# main.net
KiCad netlist of a schematic drawn in EAGLE
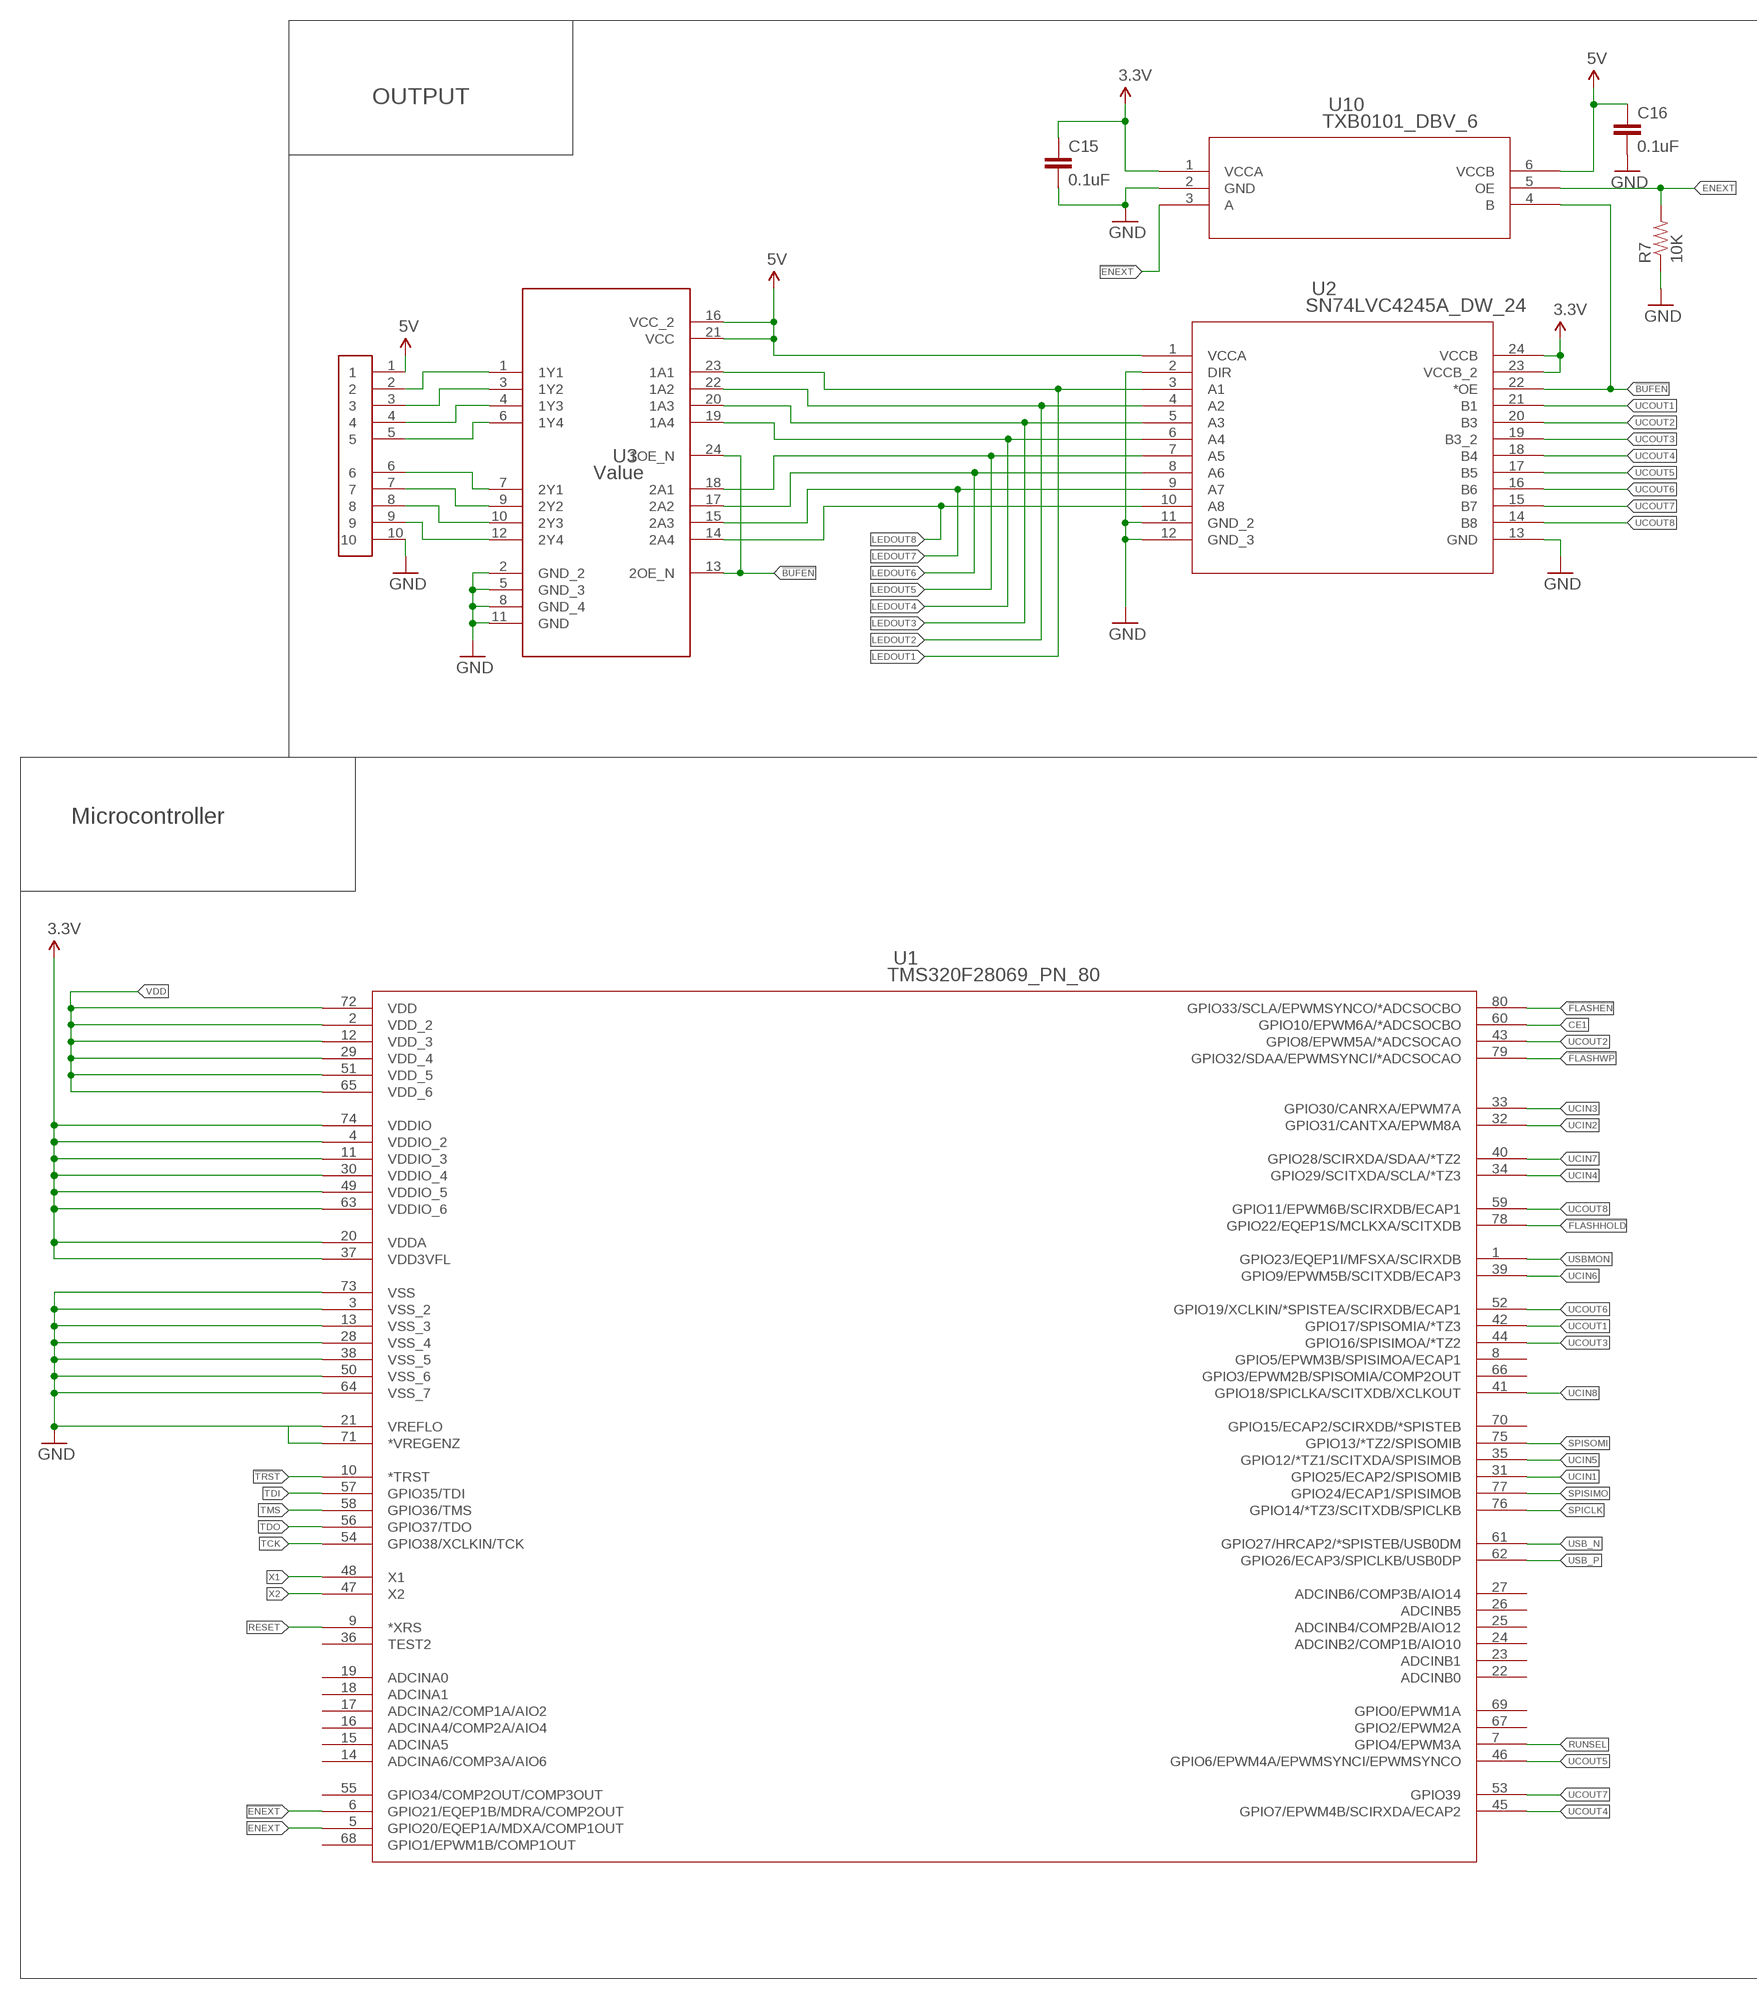
[diagram p0: schematic, sheet 1, part 1 of 2]
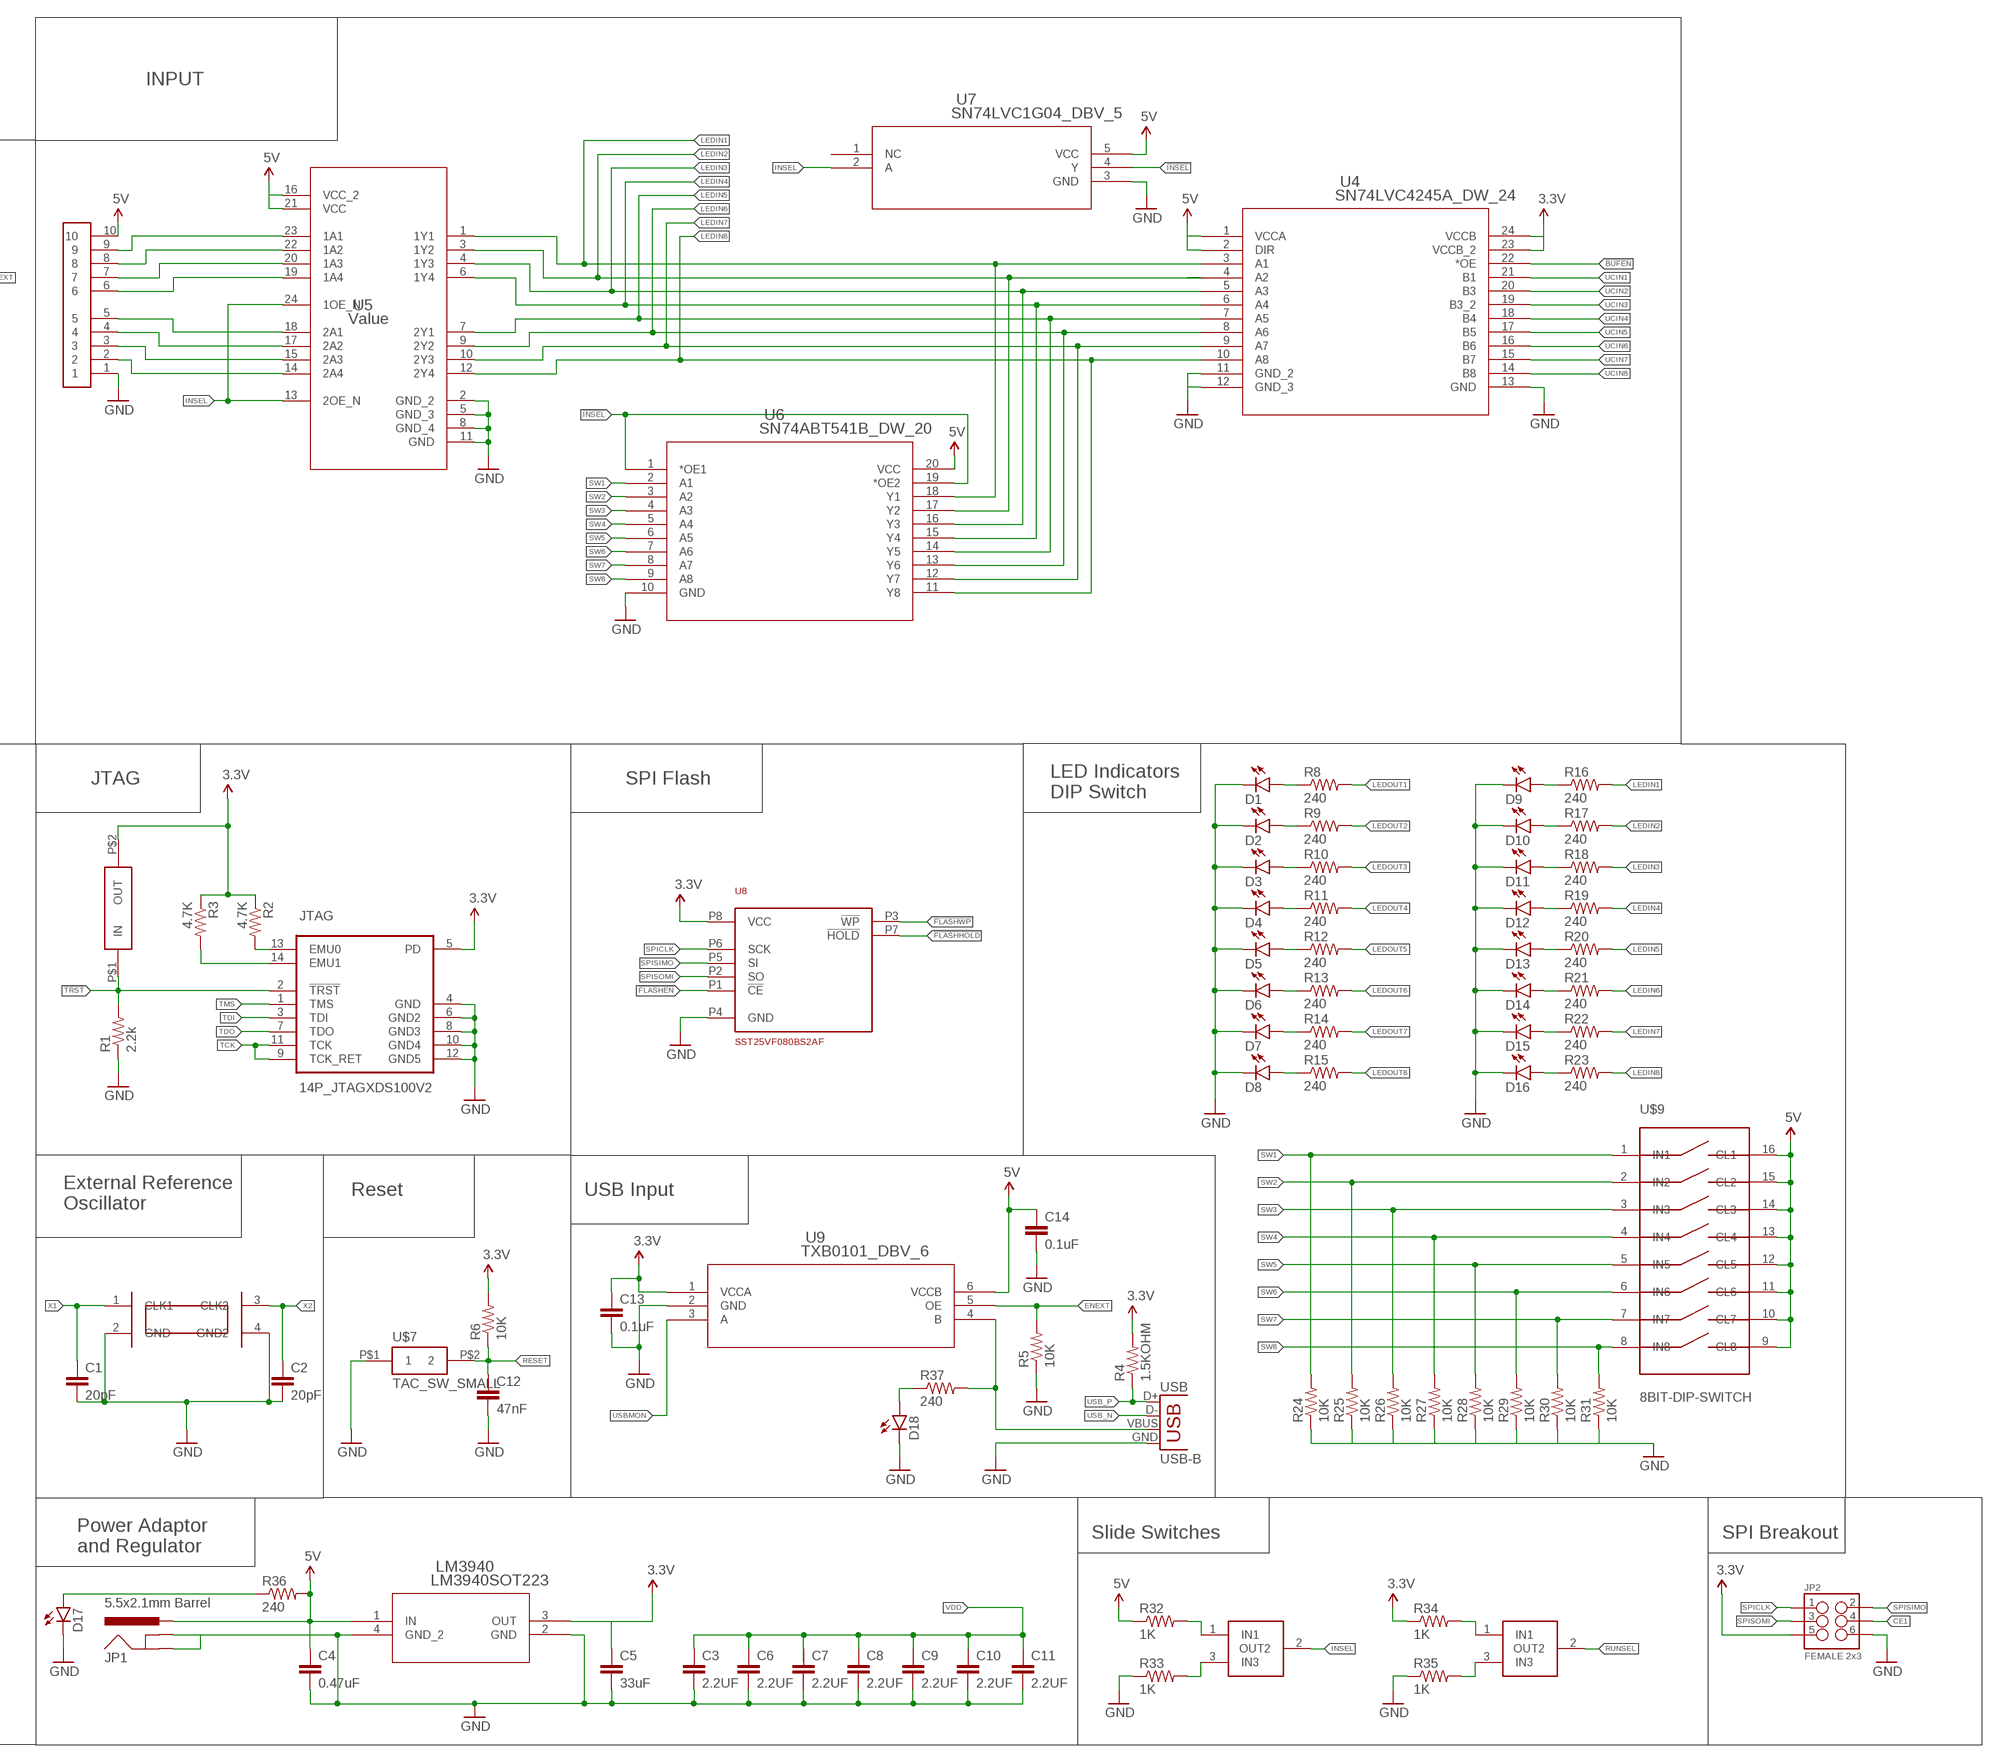
[diagram p1: schematic, sheet 1, part 2 of 2]

(export (version "E")
  (design (tool "Eeschema 10.0.6"))
  (components
    (comp (ref "!TRST!")
      (value "DIP_SWITCH_1B")
      (footprint "eagle-import:CHS-01B")
      (libsource (lib "eagle-import") (part "DIP_SWITCH_1B"))
    )
    (comp (ref "C1")
      (value "20pF")
      (footprint "eagle-import:0603-CAP")
      (libsource (lib "eagle-import") (part "18PF-50V-5%(0603)"))
    )
    (comp (ref "C2")
      (value "20pF")
      (footprint "eagle-import:0603-CAP")
      (libsource (lib "eagle-import") (part "18PF-50V-5%(0603)"))
    )
    (comp (ref "C3")
      (value "2.2UF")
      (footprint "eagle-import:1206")
      (libsource (lib "eagle-import") (part "2.2UF50V10%(1206)"))
    )
    (comp (ref "C4")
      (value "0.47uF")
      (footprint "eagle-import:0603-CAP")
      (libsource (lib "eagle-import") (part "0.22UF50V-20%,+80%(0603)"))
    )
    (comp (ref "C5")
      (value "33uF")
      (footprint "eagle-import:1206")
      (libsource (lib "eagle-import") (part "1.0UF50V10%(1206)"))
    )
    (comp (ref "C6")
      (value "2.2UF")
      (footprint "eagle-import:1206")
      (libsource (lib "eagle-import") (part "2.2UF50V10%(1206)"))
    )
    (comp (ref "C7")
      (value "2.2UF")
      (footprint "eagle-import:1206")
      (libsource (lib "eagle-import") (part "2.2UF50V10%(1206)"))
    )
    (comp (ref "C8")
      (value "2.2UF")
      (footprint "eagle-import:1206")
      (libsource (lib "eagle-import") (part "2.2UF50V10%(1206)"))
    )
    (comp (ref "C9")
      (value "2.2UF")
      (footprint "eagle-import:1206")
      (libsource (lib "eagle-import") (part "2.2UF50V10%(1206)"))
    )
    (comp (ref "C10")
      (value "2.2UF")
      (footprint "eagle-import:1206")
      (libsource (lib "eagle-import") (part "2.2UF50V10%(1206)"))
    )
    (comp (ref "C11")
      (value "2.2UF")
      (footprint "eagle-import:1206")
      (libsource (lib "eagle-import") (part "2.2UF50V10%(1206)"))
    )
    (comp (ref "C12")
      (value "47nF")
      (footprint "eagle-import:0603-CAP")
      (libsource (lib "eagle-import") (part "47NF(0.047UF/47000PF)-25V-5%(0603)SMD"))
    )
    (comp (ref "C13")
      (value "0.1uF")
      (footprint "eagle-import:1206")
      (libsource (lib "eagle-import") (part "1.0UF50V10%(1206)"))
    )
    (comp (ref "C14")
      (value "0.1uF")
      (footprint "eagle-import:1206")
      (libsource (lib "eagle-import") (part "1.0UF50V10%(1206)"))
    )
    (comp (ref "C15")
      (value "0.1uF")
      (footprint "eagle-import:1206")
      (libsource (lib "eagle-import") (part "1.0UF50V10%(1206)"))
    )
    (comp (ref "C16")
      (value "0.1uF")
      (footprint "eagle-import:1206")
      (libsource (lib "eagle-import") (part "1.0UF50V10%(1206)"))
    )
    (comp (ref "CRYSTAL")
      (value "CRYSTAL_SMD")
      (footprint "eagle-import:4SMD")
      (libsource (lib "eagle-import") (part "CRYSTAL_SMD"))
    )
    (comp (ref "D1")
      (value "LED3MM")
      (footprint "eagle-import:LED3MM")
      (libsource (lib "eagle-import") (part "LED3MM"))
    )
    (comp (ref "D2")
      (value "LED3MM")
      (footprint "eagle-import:LED3MM")
      (libsource (lib "eagle-import") (part "LED3MM"))
    )
    (comp (ref "D3")
      (value "LED3MM")
      (footprint "eagle-import:LED3MM")
      (libsource (lib "eagle-import") (part "LED3MM"))
    )
    (comp (ref "D4")
      (value "LED3MM")
      (footprint "eagle-import:LED3MM")
      (libsource (lib "eagle-import") (part "LED3MM"))
    )
    (comp (ref "D5")
      (value "LED3MM")
      (footprint "eagle-import:LED3MM")
      (libsource (lib "eagle-import") (part "LED3MM"))
    )
    (comp (ref "D6")
      (value "LED3MM")
      (footprint "eagle-import:LED3MM")
      (libsource (lib "eagle-import") (part "LED3MM"))
    )
    (comp (ref "D7")
      (value "LED3MM")
      (footprint "eagle-import:LED3MM")
      (libsource (lib "eagle-import") (part "LED3MM"))
    )
    (comp (ref "D8")
      (value "LED3MM")
      (footprint "eagle-import:LED3MM")
      (libsource (lib "eagle-import") (part "LED3MM"))
    )
    (comp (ref "D9")
      (value "LED3MM")
      (footprint "eagle-import:LED3MM")
      (libsource (lib "eagle-import") (part "LED3MM"))
    )
    (comp (ref "D10")
      (value "LED3MM")
      (footprint "eagle-import:LED3MM")
      (libsource (lib "eagle-import") (part "LED3MM"))
    )
    (comp (ref "D11")
      (value "LED3MM")
      (footprint "eagle-import:LED3MM")
      (libsource (lib "eagle-import") (part "LED3MM"))
    )
    (comp (ref "D12")
      (value "LED3MM")
      (footprint "eagle-import:LED3MM")
      (libsource (lib "eagle-import") (part "LED3MM"))
    )
    (comp (ref "D13")
      (value "LED3MM")
      (footprint "eagle-import:LED3MM")
      (libsource (lib "eagle-import") (part "LED3MM"))
    )
    (comp (ref "D14")
      (value "LED3MM")
      (footprint "eagle-import:LED3MM")
      (libsource (lib "eagle-import") (part "LED3MM"))
    )
    (comp (ref "D15")
      (value "LED3MM")
      (footprint "eagle-import:LED3MM")
      (libsource (lib "eagle-import") (part "LED3MM"))
    )
    (comp (ref "D16")
      (value "LED3MM")
      (footprint "eagle-import:LED3MM")
      (libsource (lib "eagle-import") (part "LED3MM"))
    )
    (comp (ref "D17")
      (value "LED3MM")
      (footprint "eagle-import:LED3MM")
      (libsource (lib "eagle-import") (part "LED3MM"))
    )
    (comp (ref "D18")
      (value "LED3MM")
      (footprint "eagle-import:LED3MM")
      (libsource (lib "eagle-import") (part "LED3MM"))
    )
    (comp (ref "JP1")
      (value "5.5x2.1mm Barrel")
      (footprint "eagle-import:POWER_JACK_SMD")
      (libsource (lib "eagle-import") (part "POWER_JACKSMD"))
    )
    (comp (ref "JP2")
      (value "FEMALE 2x3")
      (footprint "eagle-import:2X3")
      (libsource (lib "eagle-import") (part "M03X2FEMALE"))
    )
    (comp (ref "JTAG")
      (value "14P_JTAGXDS100V2")
      (footprint "eagle-import:2X7")
      (libsource (lib "eagle-import") (part "14P_JTAGXDS100V2"))
    )
    (comp (ref "LM3940")
      (value "LM3940SOT223")
      (footprint "eagle-import:DCY")
      (libsource (lib "eagle-import") (part "LM3940SOT223"))
    )
    (comp (ref "R1")
      (value "2.2k")
      (footprint "eagle-import:0603-RES")
      (libsource (lib "eagle-import") (part "2.2KOHM-1/10W-1%(0603)"))
    )
    (comp (ref "R2")
      (value "4.7K")
      (footprint "eagle-import:0603-RES")
      (libsource (lib "eagle-import") (part "4.7KOHM-1/10W-1%(0603)"))
    )
    (comp (ref "R3")
      (value "4.7K")
      (footprint "eagle-import:0603-RES")
      (libsource (lib "eagle-import") (part "4.7KOHM-1/10W-1%(0603)"))
    )
    (comp (ref "R4")
      (value "1.5KOHM")
      (footprint "eagle-import:0603")
      (libsource (lib "eagle-import") (part "1.5KOHM-1/10W-1%(0603)"))
    )
    (comp (ref "R5")
      (value "10K")
      (footprint "eagle-import:0603-RES")
      (libsource (lib "eagle-import") (part "10KOHM-1/10W-1%(0603)0603"))
    )
    (comp (ref "R6")
      (value "10K")
      (footprint "eagle-import:0603-RES")
      (libsource (lib "eagle-import") (part "47KOHM1/10W1%(0603)"))
    )
    (comp (ref "R7")
      (value "10K")
      (footprint "eagle-import:0603-RES")
      (libsource (lib "eagle-import") (part "10KOHM-1/10W-1%(0603)0603"))
    )
    (comp (ref "R8")
      (value "240")
      (footprint "eagle-import:0603-RES")
      (libsource (lib "eagle-import") (part "240OHM1/10W1%(0603)"))
    )
    (comp (ref "R9")
      (value "240")
      (footprint "eagle-import:0603-RES")
      (libsource (lib "eagle-import") (part "240OHM1/10W1%(0603)"))
    )
    (comp (ref "R10")
      (value "240")
      (footprint "eagle-import:0603-RES")
      (libsource (lib "eagle-import") (part "240OHM1/10W1%(0603)"))
    )
    (comp (ref "R11")
      (value "240")
      (footprint "eagle-import:0603-RES")
      (libsource (lib "eagle-import") (part "240OHM1/10W1%(0603)"))
    )
    (comp (ref "R12")
      (value "240")
      (footprint "eagle-import:0603-RES")
      (libsource (lib "eagle-import") (part "240OHM1/10W1%(0603)"))
    )
    (comp (ref "R13")
      (value "240")
      (footprint "eagle-import:0603-RES")
      (libsource (lib "eagle-import") (part "240OHM1/10W1%(0603)"))
    )
    (comp (ref "R14")
      (value "240")
      (footprint "eagle-import:0603-RES")
      (libsource (lib "eagle-import") (part "240OHM1/10W1%(0603)"))
    )
    (comp (ref "R15")
      (value "240")
      (footprint "eagle-import:0603-RES")
      (libsource (lib "eagle-import") (part "240OHM1/10W1%(0603)"))
    )
    (comp (ref "R16")
      (value "240")
      (footprint "eagle-import:0603-RES")
      (libsource (lib "eagle-import") (part "240OHM1/10W1%(0603)"))
    )
    (comp (ref "R17")
      (value "240")
      (footprint "eagle-import:0603-RES")
      (libsource (lib "eagle-import") (part "240OHM1/10W1%(0603)"))
    )
    (comp (ref "R18")
      (value "240")
      (footprint "eagle-import:0603-RES")
      (libsource (lib "eagle-import") (part "240OHM1/10W1%(0603)"))
    )
    (comp (ref "R19")
      (value "240")
      (footprint "eagle-import:0603-RES")
      (libsource (lib "eagle-import") (part "240OHM1/10W1%(0603)"))
    )
    (comp (ref "R20")
      (value "240")
      (footprint "eagle-import:0603-RES")
      (libsource (lib "eagle-import") (part "240OHM1/10W1%(0603)"))
    )
    (comp (ref "R21")
      (value "240")
      (footprint "eagle-import:0603-RES")
      (libsource (lib "eagle-import") (part "240OHM1/10W1%(0603)"))
    )
    (comp (ref "R22")
      (value "240")
      (footprint "eagle-import:0603-RES")
      (libsource (lib "eagle-import") (part "240OHM1/10W1%(0603)"))
    )
    (comp (ref "R23")
      (value "240")
      (footprint "eagle-import:0603-RES")
      (libsource (lib "eagle-import") (part "240OHM1/10W1%(0603)"))
    )
    (comp (ref "R24")
      (value "10K")
      (footprint "eagle-import:0603-RES")
      (libsource (lib "eagle-import") (part "10KOHM-1/10W-1%(0603)0603"))
    )
    (comp (ref "R25")
      (value "10K")
      (footprint "eagle-import:0603-RES")
      (libsource (lib "eagle-import") (part "10KOHM-1/10W-1%(0603)0603"))
    )
    (comp (ref "R26")
      (value "10K")
      (footprint "eagle-import:0603-RES")
      (libsource (lib "eagle-import") (part "10KOHM-1/10W-1%(0603)0603"))
    )
    (comp (ref "R27")
      (value "10K")
      (footprint "eagle-import:0603-RES")
      (libsource (lib "eagle-import") (part "10KOHM-1/10W-1%(0603)0603"))
    )
    (comp (ref "R28")
      (value "10K")
      (footprint "eagle-import:0603-RES")
      (libsource (lib "eagle-import") (part "10KOHM-1/10W-1%(0603)0603"))
    )
    (comp (ref "R29")
      (value "10K")
      (footprint "eagle-import:0603-RES")
      (libsource (lib "eagle-import") (part "10KOHM-1/10W-1%(0603)0603"))
    )
    (comp (ref "R30")
      (value "10K")
      (footprint "eagle-import:0603-RES")
      (libsource (lib "eagle-import") (part "10KOHM-1/10W-1%(0603)0603"))
    )
    (comp (ref "R31")
      (value "10K")
      (footprint "eagle-import:0603-RES")
      (libsource (lib "eagle-import") (part "10KOHM-1/10W-1%(0603)0603"))
    )
    (comp (ref "R32")
      (value "1K")
      (footprint "eagle-import:0603-RES")
      (libsource (lib "eagle-import") (part "1KOHM-1/10W-1%(0603)"))
    )
    (comp (ref "R33")
      (value "1K")
      (footprint "eagle-import:0603-RES")
      (libsource (lib "eagle-import") (part "1KOHM-1/10W-1%(0603)"))
    )
    (comp (ref "R34")
      (value "1K")
      (footprint "eagle-import:0603-RES")
      (libsource (lib "eagle-import") (part "1KOHM-1/10W-1%(0603)"))
    )
    (comp (ref "R35")
      (value "1K")
      (footprint "eagle-import:0603-RES")
      (libsource (lib "eagle-import") (part "1KOHM-1/10W-1%(0603)"))
    )
    (comp (ref "R36")
      (value "240")
      (footprint "eagle-import:0603-RES")
      (libsource (lib "eagle-import") (part "240OHM1/10W1%(0603)"))
    )
    (comp (ref "R37")
      (value "240")
      (footprint "eagle-import:0603-RES")
      (libsource (lib "eagle-import") (part "240OHM1/10W1%(0603)"))
    )
    (comp (ref "SW1")
      (value "USER_SLIDE")
      (footprint "eagle-import:USER_SLIDE_SWITCH")
      (libsource (lib "eagle-import") (part "USER_SLIDE"))
    )
    (comp (ref "SW2")
      (value "USER_SLIDE")
      (footprint "eagle-import:USER_SLIDE_SWITCH")
      (libsource (lib "eagle-import") (part "USER_SLIDE"))
    )
    (comp (ref "U$4")
      (value "8PIN_SOCKET")
      (footprint "eagle-import:CONN-8PIN")
      (libsource (lib "eagle-import") (part "8PIN_SOCKET"))
    )
    (comp (ref "U$7")
      (value "TAC_SW_SMALL")
      (footprint "eagle-import:1000P")
      (libsource (lib "eagle-import") (part "TAC_SW_SMALL"))
    )
    (comp (ref "U$8")
      (value "8PIN_SOCKET")
      (footprint "eagle-import:CONN-8PIN")
      (libsource (lib "eagle-import") (part "8PIN_SOCKET"))
    )
    (comp (ref "U$9")
      (value "8BIT-DIP-SWITCH")
      (footprint "eagle-import:SPST-DIPS-SW")
      (libsource (lib "eagle-import") (part "8BIT-DIP-SWITCH"))
    )
    (comp (ref "U1")
      (value "TMS320F28069_PN_80")
      (footprint "eagle-import:PN80")
      (fields
        (field (name "GENERIC_PART_NUMBER") "TMS320F28069")
        (field (name "MANUFACTURER") "Texas Instruments")
        (field (name "MANUFACTURER_PART_NUMBER") "tms320f28069_pn_80")
      )
      (libsource (lib "eagle-import") (part "TMS320F28069_PN_80"))
    )
    (comp (ref "U2")
      (value "SN74LVC4245A_DW_24")
      (footprint "eagle-import:DW24")
      (fields
        (field (name "GENERIC_PART_NUMBER") "SN74LVC4245A")
        (field (name "MANUFACTURER") "Texas Instruments")
        (field (name "MANUFACTURER_PART_NUMBER") "sn74lvc4245a_dw_24")
      )
      (libsource (lib "eagle-import") (part "SN74LVC4245A_DW_24"))
    )
    (comp (ref "U3")
      (value "Value")
      (footprint "eagle-import:DW0024A_N")
      (fields (field (name "MANUFACTURER") "Texas Instruments") (field (name "PARTNUMBER") "SN64BCT25244DW"))
      (libsource (lib "eagle-import") (part "SN64BCT25244DW"))
    )
    (comp (ref "U4")
      (value "SN74LVC4245A_DW_24")
      (footprint "eagle-import:DW24")
      (fields
        (field (name "GENERIC_PART_NUMBER") "SN74LVC4245A")
        (field (name "MANUFACTURER") "Texas Instruments")
        (field (name "MANUFACTURER_PART_NUMBER") "sn74lvc4245a_dw_24")
      )
      (libsource (lib "eagle-import") (part "SN74LVC4245A_DW_24"))
    )
    (comp (ref "U5")
      (value "Value")
      (footprint "eagle-import:DW0024A_N")
      (fields (field (name "MANUFACTURER") "Texas Instruments") (field (name "PARTNUMBER") "SN64BCT25244DW"))
      (libsource (lib "eagle-import") (part "SN64BCT25244DW"))
    )
    (comp (ref "U6")
      (value "SN74ABT541B_DW_20")
      (footprint "eagle-import:DW20")
      (fields
        (field (name "GENERIC_PART_NUMBER") "SN74ABT541B")
        (field (name "MANUFACTURER") "Texas Instruments")
      )
      (libsource (lib "eagle-import") (part "SN74ABT541B_DW_20"))
    )
    (comp (ref "U7")
      (value "SN74LVC1G04_DBV_5")
      (footprint "eagle-import:DBV5")
      (fields
        (field (name "GENERIC_PART_NUMBER") "SN74LVC1G04")
        (field (name "MANUFACTURER") "Texas Instruments")
        (field (name "MANUFACTURER_PART_NUMBER") "sn74lvc1g04_dbv_5")
      )
      (libsource (lib "eagle-import") (part "SN74LVC1G04_DBV_5"))
    )
    (comp (ref "U8")
      (value "SST25VF080BS2AF")
      (footprint "eagle-import:S2AE_F")
      (libsource (lib "eagle-import") (part "SST25VF080BS2AF"))
    )
    (comp (ref "U9")
      (value "TXB0101_DBV_6")
      (footprint "eagle-import:DBV6")
      (fields
        (field (name "GENERIC_PART_NUMBER") "TXB0101")
        (field (name "MANUFACTURER") "Texas Instruments")
        (field (name "MANUFACTURER_PART_NUMBER") "txb0101_dbv_6")
      )
      (libsource (lib "eagle-import") (part "TXB0101_DBV_6"))
    )
    (comp (ref "U10")
      (value "TXB0101_DBV_6")
      (footprint "eagle-import:DBV6")
      (fields
        (field (name "GENERIC_PART_NUMBER") "TXB0101")
        (field (name "MANUFACTURER") "Texas Instruments")
        (field (name "MANUFACTURER_PART_NUMBER") "txb0101_dbv_6")
      )
      (libsource (lib "eagle-import") (part "TXB0101_DBV_6"))
    )
    (comp (ref "USB")
      (value "USB-B")
      (footprint "eagle-import:USB-B-PTH")
      (libsource (lib "eagle-import") (part "USBPTH"))
    )
  )
  (nets
    (net (code "1") (name "/~{BUFEN}") (class "Default")
      (node (ref "U10") (pin "4") (pinfunction "B_4") (pintype "bidirectional"))
      (node (ref "U2") (pin "22") (pinfunction "*OE_22") (pintype "input"))
      (node (ref "U3") (pin "13") (pinfunction "2OE_N_13") (pintype "input"))
      (node (ref "U3") (pin "24") (pinfunction "1OE_N_24") (pintype "input"))
      (node (ref "U4") (pin "22") (pinfunction "*OE_22") (pintype "input"))
    )
    (net (code "2") (name "/~{ENEXT}") (class "Default")
      (node (ref "U1") (pin "6") (pinfunction "GPIO21/EQEP1B/MDRA/COMP2OUT_6") (pintype "bidirectional"))
      (node (ref "U10") (pin "3") (pinfunction "A_3") (pintype "bidirectional"))
    )
    (net (code "3") (name "/~{FLASHEN}") (class "Default")
      (node (ref "U1") (pin "80") (pinfunction "GPIO33/SCLA/EPWMSYNCO/*ADCSOCBO_80") (pintype "bidirectional"))
      (node (ref "U8") (pin "P1") (pinfunction "~{CE}_P1") (pintype "bidirectional"))
    )
    (net (code "4") (name "/~{FLASHHOLD}") (class "Default")
      (node (ref "U1") (pin "78") (pinfunction "GPIO22/EQEP1S/MCLKXA/SCITXDB_78") (pintype "bidirectional"))
      (node (ref "U8") (pin "P7") (pinfunction "~{HOLD}_P7") (pintype "bidirectional"))
    )
    (net (code "5") (name "/~{FLASHWP}") (class "Default")
      (node (ref "U1") (pin "79") (pinfunction "GPIO32/SDAA/EPWMSYNCI/*ADCSOCAO_79") (pintype "bidirectional"))
      (node (ref "U8") (pin "P3") (pinfunction "~{WP}_P3") (pintype "bidirectional"))
    )
    (net (code "6") (name "/~{INSEL}") (class "Default")
      (node (ref "U6") (pin "1") (pinfunction "*OE1_1") (pintype "input"))
      (node (ref "U6") (pin "19") (pinfunction "*OE2_19") (pintype "input"))
      (node (ref "U7") (pin "4") (pinfunction "Y_4") (pintype "output"))
    )
    (net (code "7") (name "/~{TRST}") (class "Default")
      (node (ref "!TRST!") (pin "P$1") (pinfunction "IN_P$1") (pintype "bidirectional"))
      (node (ref "JTAG") (pin "2") (pinfunction "~{TRST}_2") (pintype "bidirectional"))
      (node (ref "R1") (pin "2") (pinfunction "2_2") (pintype "passive"))
      (node (ref "U1") (pin "10") (pinfunction "*TRST_10") (pintype "input"))
    )
    (net (code "8") (name "3.3V") (class "Default")
      (node (ref "!TRST!") (pin "P$2") (pinfunction "OUT_P$2") (pintype "bidirectional"))
      (node (ref "C13") (pin "1") (pinfunction "1_1") (pintype "passive"))
      (node (ref "C15") (pin "1") (pinfunction "1_1") (pintype "passive"))
      (node (ref "C5") (pin "1") (pinfunction "1_1") (pintype "passive"))
      (node (ref "JP2") (pin "5") (pinfunction "5_5") (pintype "bidirectional"))
      (node (ref "JTAG") (pin "5") (pinfunction "PD_5") (pintype "bidirectional"))
      (node (ref "LM3940") (pin "3") (pinfunction "OUT_3") (pintype "output"))
      (node (ref "R2") (pin "1") (pinfunction "1_1") (pintype "passive"))
      (node (ref "R3") (pin "1") (pinfunction "1_1") (pintype "passive"))
      (node (ref "R34") (pin "1") (pinfunction "1_1") (pintype "passive"))
      (node (ref "R4") (pin "2") (pinfunction "2_2") (pintype "passive"))
      (node (ref "R6") (pin "2") (pinfunction "2_2") (pintype "passive"))
      (node (ref "U1") (pin "11") (pinfunction "VDDIO_3_11") (pintype "power_in"))
      (node (ref "U1") (pin "20") (pinfunction "VDDA_20") (pintype "power_in"))
      (node (ref "U1") (pin "30") (pinfunction "VDDIO_4_30") (pintype "power_in"))
      (node (ref "U1") (pin "37") (pinfunction "VDD3VFL_37") (pintype "power_in"))
      (node (ref "U1") (pin "4") (pinfunction "VDDIO_2_4") (pintype "power_in"))
      (node (ref "U1") (pin "49") (pinfunction "VDDIO_5_49") (pintype "power_in"))
      (node (ref "U1") (pin "63") (pinfunction "VDDIO_6_63") (pintype "power_in"))
      (node (ref "U1") (pin "74") (pinfunction "VDDIO_74") (pintype "power_in"))
      (node (ref "U10") (pin "1") (pinfunction "VCCA_1") (pintype "power_in"))
      (node (ref "U2") (pin "23") (pinfunction "VCCB_2_23") (pintype "power_in"))
      (node (ref "U2") (pin "24") (pinfunction "VCCB_24") (pintype "power_in"))
      (node (ref "U4") (pin "23") (pinfunction "VCCB_2_23") (pintype "power_in"))
      (node (ref "U4") (pin "24") (pinfunction "VCCB_24") (pintype "power_in"))
      (node (ref "U8") (pin "P8") (pinfunction "VCC_P8") (pintype "bidirectional"))
      (node (ref "U9") (pin "1") (pinfunction "VCCA_1") (pintype "power_in"))
    )
    (net (code "9") (name "5V") (class "Default")
      (node (ref "C14") (pin "1") (pinfunction "1_1") (pintype "passive"))
      (node (ref "C16") (pin "1") (pinfunction "1_1") (pintype "passive"))
      (node (ref "C4") (pin "1") (pinfunction "1_1") (pintype "passive"))
      (node (ref "JP1") (pin "VIN0") (pinfunction "PWR_VIN0") (pintype "bidirectional"))
      (node (ref "LM3940") (pin "1") (pinfunction "IN_1") (pintype "input"))
      (node (ref "R32") (pin "1") (pinfunction "1_1") (pintype "passive"))
      (node (ref "R36") (pin "2") (pinfunction "2_2") (pintype "passive"))
      (node (ref "U$4") (pin "1") (pinfunction "1_1") (pintype "bidirectional"))
      (node (ref "U$8") (pin "10") (pinfunction "10_10") (pintype "bidirectional"))
      (node (ref "U$9") (pin "10") (pinfunction "CL7_10") (pintype "bidirectional"))
      (node (ref "U$9") (pin "11") (pinfunction "CL6_11") (pintype "bidirectional"))
      (node (ref "U$9") (pin "12") (pinfunction "CL5_12") (pintype "bidirectional"))
      (node (ref "U$9") (pin "13") (pinfunction "CL4_13") (pintype "bidirectional"))
      (node (ref "U$9") (pin "14") (pinfunction "CL3_14") (pintype "bidirectional"))
      (node (ref "U$9") (pin "15") (pinfunction "CL2_15") (pintype "bidirectional"))
      (node (ref "U$9") (pin "16") (pinfunction "CL1_16") (pintype "bidirectional"))
      (node (ref "U$9") (pin "9") (pinfunction "CL8_9") (pintype "bidirectional"))
      (node (ref "U10") (pin "6") (pinfunction "VCCB_6") (pintype "power_in"))
      (node (ref "U2") (pin "1") (pinfunction "VCCA_1") (pintype "power_in"))
      (node (ref "U3") (pin "16") (pinfunction "VCC_2_16") (pintype "power_in"))
      (node (ref "U3") (pin "21") (pinfunction "VCC_21") (pintype "power_in"))
      (node (ref "U4") (pin "1") (pinfunction "VCCA_1") (pintype "power_in"))
      (node (ref "U4") (pin "2") (pinfunction "DIR_2") (pintype "input"))
      (node (ref "U5") (pin "16") (pinfunction "VCC_2_16") (pintype "power_in"))
      (node (ref "U5") (pin "21") (pinfunction "VCC_21") (pintype "power_in"))
      (node (ref "U6") (pin "20") (pinfunction "VCC_20") (pintype "power_in"))
      (node (ref "U7") (pin "5") (pinfunction "VCC_5") (pintype "power_in"))
      (node (ref "U9") (pin "6") (pinfunction "VCCB_6") (pintype "power_in"))
    )
    (net (code "10") (name "CE1") (class "Default")
      (node (ref "JP2") (pin "4") (pinfunction "4_4") (pintype "bidirectional"))
      (node (ref "U1") (pin "60") (pinfunction "GPIO10/EPWM6A/*ADCSOCBO_60") (pintype "bidirectional"))
    )
    (net (code "11") (name "ENEXT") (class "Default")
      (node (ref "R5") (pin "2") (pinfunction "2_2") (pintype "passive"))
      (node (ref "R7") (pin "2") (pinfunction "2_2") (pintype "passive"))
      (node (ref "U1") (pin "5") (pinfunction "GPIO20/EQEP1A/MDXA/COMP1OUT_5") (pintype "bidirectional"))
      (node (ref "U10") (pin "5") (pinfunction "OE_5") (pintype "output"))
      (node (ref "U9") (pin "5") (pinfunction "OE_5") (pintype "output"))
    )
    (net (code "12") (name "GND") (class "Default")
      (node (ref "C1") (pin "2") (pinfunction "2_2") (pintype "passive"))
      (node (ref "C10") (pin "2") (pinfunction "2_2") (pintype "passive"))
      (node (ref "C11") (pin "2") (pinfunction "2_2") (pintype "passive"))
      (node (ref "C12") (pin "2") (pinfunction "2_2") (pintype "passive"))
      (node (ref "C13") (pin "2") (pinfunction "2_2") (pintype "passive"))
      (node (ref "C14") (pin "2") (pinfunction "2_2") (pintype "passive"))
      (node (ref "C15") (pin "2") (pinfunction "2_2") (pintype "passive"))
      (node (ref "C16") (pin "2") (pinfunction "2_2") (pintype "passive"))
      (node (ref "C2") (pin "2") (pinfunction "2_2") (pintype "passive"))
      (node (ref "C3") (pin "2") (pinfunction "2_2") (pintype "passive"))
      (node (ref "C4") (pin "2") (pinfunction "2_2") (pintype "passive"))
      (node (ref "C5") (pin "2") (pinfunction "2_2") (pintype "passive"))
      (node (ref "C6") (pin "2") (pinfunction "2_2") (pintype "passive"))
      (node (ref "C7") (pin "2") (pinfunction "2_2") (pintype "passive"))
      (node (ref "C8") (pin "2") (pinfunction "2_2") (pintype "passive"))
      (node (ref "C9") (pin "2") (pinfunction "2_2") (pintype "passive"))
      (node (ref "CRYSTAL") (pin "2") (pinfunction "GND_2") (pintype "bidirectional"))
      (node (ref "CRYSTAL") (pin "4") (pinfunction "GND2_4") (pintype "bidirectional"))
      (node (ref "D1") (pin "K") (pinfunction "C_K") (pintype "passive"))
      (node (ref "D10") (pin "K") (pinfunction "C_K") (pintype "passive"))
      (node (ref "D11") (pin "K") (pinfunction "C_K") (pintype "passive"))
      (node (ref "D12") (pin "K") (pinfunction "C_K") (pintype "passive"))
      (node (ref "D13") (pin "K") (pinfunction "C_K") (pintype "passive"))
      (node (ref "D14") (pin "K") (pinfunction "C_K") (pintype "passive"))
      (node (ref "D15") (pin "K") (pinfunction "C_K") (pintype "passive"))
      (node (ref "D16") (pin "K") (pinfunction "C_K") (pintype "passive"))
      (node (ref "D17") (pin "K") (pinfunction "C_K") (pintype "passive"))
      (node (ref "D18") (pin "K") (pinfunction "C_K") (pintype "passive"))
      (node (ref "D2") (pin "K") (pinfunction "C_K") (pintype "passive"))
      (node (ref "D3") (pin "K") (pinfunction "C_K") (pintype "passive"))
      (node (ref "D4") (pin "K") (pinfunction "C_K") (pintype "passive"))
      (node (ref "D5") (pin "K") (pinfunction "C_K") (pintype "passive"))
      (node (ref "D6") (pin "K") (pinfunction "C_K") (pintype "passive"))
      (node (ref "D7") (pin "K") (pinfunction "C_K") (pintype "passive"))
      (node (ref "D8") (pin "K") (pinfunction "C_K") (pintype "passive"))
      (node (ref "D9") (pin "K") (pinfunction "C_K") (pintype "passive"))
      (node (ref "JP1") (pin "GND") (pinfunction "GNDBREAK_GND") (pintype "bidirectional"))
      (node (ref "JP1") (pin "P$4") (pinfunction "GND_P$4") (pintype "bidirectional"))
      (node (ref "JP2") (pin "6") (pinfunction "6_6") (pintype "bidirectional"))
      (node (ref "JTAG") (pin "10") (pinfunction "GND4_10") (pintype "bidirectional"))
      (node (ref "JTAG") (pin "12") (pinfunction "GND5_12") (pintype "bidirectional"))
      (node (ref "JTAG") (pin "4") (pinfunction "GND_4") (pintype "bidirectional"))
      (node (ref "JTAG") (pin "6") (pinfunction "GND2_6") (pintype "bidirectional"))
      (node (ref "JTAG") (pin "8") (pinfunction "GND3_8") (pintype "bidirectional"))
      (node (ref "LM3940") (pin "2") (pinfunction "GND_2") (pintype "passive"))
      (node (ref "LM3940") (pin "4") (pinfunction "GND_2_4") (pintype "passive"))
      (node (ref "R1") (pin "1") (pinfunction "1_1") (pintype "passive"))
      (node (ref "R24") (pin "1") (pinfunction "1_1") (pintype "passive"))
      (node (ref "R25") (pin "1") (pinfunction "1_1") (pintype "passive"))
      (node (ref "R26") (pin "1") (pinfunction "1_1") (pintype "passive"))
      (node (ref "R27") (pin "1") (pinfunction "1_1") (pintype "passive"))
      (node (ref "R28") (pin "1") (pinfunction "1_1") (pintype "passive"))
      (node (ref "R29") (pin "1") (pinfunction "1_1") (pintype "passive"))
      (node (ref "R30") (pin "1") (pinfunction "1_1") (pintype "passive"))
      (node (ref "R31") (pin "1") (pinfunction "1_1") (pintype "passive"))
      (node (ref "R33") (pin "1") (pinfunction "1_1") (pintype "passive"))
      (node (ref "R35") (pin "1") (pinfunction "1_1") (pintype "passive"))
      (node (ref "R5") (pin "1") (pinfunction "1_1") (pintype "passive"))
      (node (ref "R7") (pin "1") (pinfunction "1_1") (pintype "passive"))
      (node (ref "U$4") (pin "10") (pinfunction "10_10") (pintype "bidirectional"))
      (node (ref "U$7") (pin "P$1") (pinfunction "1_P$1") (pintype "bidirectional"))
      (node (ref "U$8") (pin "1") (pinfunction "1_1") (pintype "bidirectional"))
      (node (ref "U1") (pin "13") (pinfunction "VSS_3_13") (pintype "power_in"))
      (node (ref "U1") (pin "21") (pinfunction "VREFLO_21") (pintype "passive"))
      (node (ref "U1") (pin "28") (pinfunction "VSS_4_28") (pintype "power_in"))
      (node (ref "U1") (pin "3") (pinfunction "VSS_2_3") (pintype "power_in"))
      (node (ref "U1") (pin "38") (pinfunction "VSS_5_38") (pintype "power_in"))
      (node (ref "U1") (pin "50") (pinfunction "VSS_6_50") (pintype "power_in"))
      (node (ref "U1") (pin "64") (pinfunction "VSS_7_64") (pintype "power_in"))
      (node (ref "U1") (pin "71") (pinfunction "*VREGENZ_71") (pintype "input"))
      (node (ref "U1") (pin "73") (pinfunction "VSS_73") (pintype "power_in"))
      (node (ref "U10") (pin "2") (pinfunction "GND_2") (pintype "power_in"))
      (node (ref "U2") (pin "11") (pinfunction "GND_2_11") (pintype "power_in"))
      (node (ref "U2") (pin "12") (pinfunction "GND_3_12") (pintype "power_in"))
      (node (ref "U2") (pin "13") (pinfunction "GND_13") (pintype "power_in"))
      (node (ref "U2") (pin "2") (pinfunction "DIR_2") (pintype "input"))
      (node (ref "U3") (pin "11") (pinfunction "GND_11") (pintype "power_in"))
      (node (ref "U3") (pin "2") (pinfunction "GND_2_2") (pintype "power_in"))
      (node (ref "U3") (pin "5") (pinfunction "GND_3_5") (pintype "power_in"))
      (node (ref "U3") (pin "8") (pinfunction "GND_4_8") (pintype "power_in"))
      (node (ref "U4") (pin "11") (pinfunction "GND_2_11") (pintype "power_in"))
      (node (ref "U4") (pin "12") (pinfunction "GND_3_12") (pintype "power_in"))
      (node (ref "U4") (pin "13") (pinfunction "GND_13") (pintype "power_in"))
      (node (ref "U5") (pin "11") (pinfunction "GND_11") (pintype "power_in"))
      (node (ref "U5") (pin "2") (pinfunction "GND_2_2") (pintype "power_in"))
      (node (ref "U5") (pin "5") (pinfunction "GND_3_5") (pintype "power_in"))
      (node (ref "U5") (pin "8") (pinfunction "GND_4_8") (pintype "power_in"))
      (node (ref "U6") (pin "10") (pinfunction "GND_10") (pintype "power_in"))
      (node (ref "U7") (pin "3") (pinfunction "GND_3") (pintype "power_in"))
      (node (ref "U8") (pin "P4") (pinfunction "GND_P4") (pintype "bidirectional"))
      (node (ref "U9") (pin "2") (pinfunction "GND_2") (pintype "power_in"))
      (node (ref "USB") (pin "GND") (pinfunction "GND_GND") (pintype "bidirectional"))
    )
    (net (code "13") (name "INSEL") (class "Default")
      (node (ref "SW1") (pin "2") (pinfunction "OUT2_2") (pintype "bidirectional"))
      (node (ref "U5") (pin "13") (pinfunction "2OE_N_13") (pintype "input"))
      (node (ref "U5") (pin "24") (pinfunction "1OE_N_24") (pintype "input"))
      (node (ref "U7") (pin "2") (pinfunction "A_2") (pintype "input"))
    )
    (net (code "14") (name "LEDIN1") (class "Default")
      (node (ref "R16") (pin "2") (pinfunction "2_2") (pintype "passive"))
      (node (ref "U4") (pin "3") (pinfunction "A1_3") (pintype "bidirectional"))
      (node (ref "U5") (pin "1") (pinfunction "1Y1_1") (pintype "tri_state"))
      (node (ref "U6") (pin "18") (pinfunction "Y1_18") (pintype "output"))
    )
    (net (code "15") (name "LEDIN2") (class "Default")
      (node (ref "R17") (pin "2") (pinfunction "2_2") (pintype "passive"))
      (node (ref "U4") (pin "4") (pinfunction "A2_4") (pintype "bidirectional"))
      (node (ref "U5") (pin "3") (pinfunction "1Y2_3") (pintype "tri_state"))
      (node (ref "U6") (pin "17") (pinfunction "Y2_17") (pintype "output"))
    )
    (net (code "16") (name "LEDIN3") (class "Default")
      (node (ref "R18") (pin "2") (pinfunction "2_2") (pintype "passive"))
      (node (ref "U4") (pin "5") (pinfunction "A3_5") (pintype "bidirectional"))
      (node (ref "U5") (pin "4") (pinfunction "1Y3_4") (pintype "tri_state"))
      (node (ref "U6") (pin "16") (pinfunction "Y3_16") (pintype "output"))
    )
    (net (code "17") (name "LEDIN4") (class "Default")
      (node (ref "R19") (pin "2") (pinfunction "2_2") (pintype "passive"))
      (node (ref "U4") (pin "6") (pinfunction "A4_6") (pintype "bidirectional"))
      (node (ref "U5") (pin "6") (pinfunction "1Y4_6") (pintype "tri_state"))
      (node (ref "U6") (pin "15") (pinfunction "Y4_15") (pintype "output"))
    )
    (net (code "18") (name "LEDIN5") (class "Default")
      (node (ref "R20") (pin "2") (pinfunction "2_2") (pintype "passive"))
      (node (ref "U4") (pin "7") (pinfunction "A5_7") (pintype "bidirectional"))
      (node (ref "U5") (pin "7") (pinfunction "2Y1_7") (pintype "tri_state"))
      (node (ref "U6") (pin "14") (pinfunction "Y5_14") (pintype "output"))
    )
    (net (code "19") (name "LEDIN6") (class "Default")
      (node (ref "R21") (pin "2") (pinfunction "2_2") (pintype "passive"))
      (node (ref "U4") (pin "8") (pinfunction "A6_8") (pintype "bidirectional"))
      (node (ref "U5") (pin "9") (pinfunction "2Y2_9") (pintype "tri_state"))
      (node (ref "U6") (pin "13") (pinfunction "Y6_13") (pintype "output"))
    )
    (net (code "20") (name "LEDIN7") (class "Default")
      (node (ref "R22") (pin "2") (pinfunction "2_2") (pintype "passive"))
      (node (ref "U4") (pin "9") (pinfunction "A7_9") (pintype "bidirectional"))
      (node (ref "U5") (pin "10") (pinfunction "2Y3_10") (pintype "tri_state"))
      (node (ref "U6") (pin "12") (pinfunction "Y7_12") (pintype "output"))
    )
    (net (code "21") (name "LEDIN8") (class "Default")
      (node (ref "R23") (pin "2") (pinfunction "2_2") (pintype "passive"))
      (node (ref "U4") (pin "10") (pinfunction "A8_10") (pintype "bidirectional"))
      (node (ref "U5") (pin "12") (pinfunction "2Y4_12") (pintype "tri_state"))
      (node (ref "U6") (pin "11") (pinfunction "Y8_11") (pintype "output"))
    )
    (net (code "22") (name "LEDOUT1") (class "Default")
      (node (ref "R8") (pin "2") (pinfunction "2_2") (pintype "passive"))
      (node (ref "U2") (pin "3") (pinfunction "A1_3") (pintype "bidirectional"))
      (node (ref "U3") (pin "23") (pinfunction "1A1_23") (pintype "input"))
    )
    (net (code "23") (name "LEDOUT2") (class "Default")
      (node (ref "R9") (pin "2") (pinfunction "2_2") (pintype "passive"))
      (node (ref "U2") (pin "4") (pinfunction "A2_4") (pintype "bidirectional"))
      (node (ref "U3") (pin "22") (pinfunction "1A2_22") (pintype "input"))
    )
    (net (code "24") (name "LEDOUT3") (class "Default")
      (node (ref "R10") (pin "2") (pinfunction "2_2") (pintype "passive"))
      (node (ref "U2") (pin "5") (pinfunction "A3_5") (pintype "bidirectional"))
      (node (ref "U3") (pin "20") (pinfunction "1A3_20") (pintype "input"))
    )
    (net (code "25") (name "LEDOUT4") (class "Default")
      (node (ref "R11") (pin "2") (pinfunction "2_2") (pintype "passive"))
      (node (ref "U2") (pin "6") (pinfunction "A4_6") (pintype "bidirectional"))
      (node (ref "U3") (pin "19") (pinfunction "1A4_19") (pintype "input"))
    )
    (net (code "26") (name "LEDOUT5") (class "Default")
      (node (ref "R12") (pin "2") (pinfunction "2_2") (pintype "passive"))
      (node (ref "U2") (pin "7") (pinfunction "A5_7") (pintype "bidirectional"))
      (node (ref "U3") (pin "18") (pinfunction "2A1_18") (pintype "input"))
    )
    (net (code "27") (name "LEDOUT6") (class "Default")
      (node (ref "R13") (pin "2") (pinfunction "2_2") (pintype "passive"))
      (node (ref "U2") (pin "8") (pinfunction "A6_8") (pintype "bidirectional"))
      (node (ref "U3") (pin "17") (pinfunction "2A2_17") (pintype "input"))
    )
    (net (code "28") (name "LEDOUT7") (class "Default")
      (node (ref "R14") (pin "2") (pinfunction "2_2") (pintype "passive"))
      (node (ref "U2") (pin "9") (pinfunction "A7_9") (pintype "bidirectional"))
      (node (ref "U3") (pin "15") (pinfunction "2A3_15") (pintype "input"))
    )
    (net (code "29") (name "LEDOUT8") (class "Default")
      (node (ref "R15") (pin "2") (pinfunction "2_2") (pintype "passive"))
      (node (ref "U2") (pin "10") (pinfunction "A8_10") (pintype "bidirectional"))
      (node (ref "U3") (pin "14") (pinfunction "2A4_14") (pintype "input"))
    )
    (net (code "30") (name "Net-(D1-PadA)") (class "Default")
      (node (ref "D1") (pin "A") (pinfunction "A_A") (pintype "passive"))
      (node (ref "R8") (pin "1") (pinfunction "1_1") (pintype "passive"))
    )
    (net (code "31") (name "Net-(D2-PadA)") (class "Default")
      (node (ref "D2") (pin "A") (pinfunction "A_A") (pintype "passive"))
      (node (ref "R9") (pin "1") (pinfunction "1_1") (pintype "passive"))
    )
    (net (code "32") (name "Net-(D3-PadA)") (class "Default")
      (node (ref "D3") (pin "A") (pinfunction "A_A") (pintype "passive"))
      (node (ref "R10") (pin "1") (pinfunction "1_1") (pintype "passive"))
    )
    (net (code "33") (name "Net-(D4-PadA)") (class "Default")
      (node (ref "D4") (pin "A") (pinfunction "A_A") (pintype "passive"))
      (node (ref "R11") (pin "1") (pinfunction "1_1") (pintype "passive"))
    )
    (net (code "34") (name "Net-(D5-PadA)") (class "Default")
      (node (ref "D5") (pin "A") (pinfunction "A_A") (pintype "passive"))
      (node (ref "R12") (pin "1") (pinfunction "1_1") (pintype "passive"))
    )
    (net (code "35") (name "Net-(D6-PadA)") (class "Default")
      (node (ref "D6") (pin "A") (pinfunction "A_A") (pintype "passive"))
      (node (ref "R13") (pin "1") (pinfunction "1_1") (pintype "passive"))
    )
    (net (code "36") (name "Net-(D7-PadA)") (class "Default")
      (node (ref "D7") (pin "A") (pinfunction "A_A") (pintype "passive"))
      (node (ref "R14") (pin "1") (pinfunction "1_1") (pintype "passive"))
    )
    (net (code "37") (name "Net-(D8-PadA)") (class "Default")
      (node (ref "D8") (pin "A") (pinfunction "A_A") (pintype "passive"))
      (node (ref "R15") (pin "1") (pinfunction "1_1") (pintype "passive"))
    )
    (net (code "38") (name "Net-(D9-PadA)") (class "Default")
      (node (ref "D9") (pin "A") (pinfunction "A_A") (pintype "passive"))
      (node (ref "R16") (pin "1") (pinfunction "1_1") (pintype "passive"))
    )
    (net (code "39") (name "Net-(D10-PadA)") (class "Default")
      (node (ref "D10") (pin "A") (pinfunction "A_A") (pintype "passive"))
      (node (ref "R17") (pin "1") (pinfunction "1_1") (pintype "passive"))
    )
    (net (code "40") (name "Net-(D11-PadA)") (class "Default")
      (node (ref "D11") (pin "A") (pinfunction "A_A") (pintype "passive"))
      (node (ref "R18") (pin "1") (pinfunction "1_1") (pintype "passive"))
    )
    (net (code "41") (name "Net-(D12-PadA)") (class "Default")
      (node (ref "D12") (pin "A") (pinfunction "A_A") (pintype "passive"))
      (node (ref "R19") (pin "1") (pinfunction "1_1") (pintype "passive"))
    )
    (net (code "42") (name "Net-(D13-PadA)") (class "Default")
      (node (ref "D13") (pin "A") (pinfunction "A_A") (pintype "passive"))
      (node (ref "R20") (pin "1") (pinfunction "1_1") (pintype "passive"))
    )
    (net (code "43") (name "Net-(D14-PadA)") (class "Default")
      (node (ref "D14") (pin "A") (pinfunction "A_A") (pintype "passive"))
      (node (ref "R21") (pin "1") (pinfunction "1_1") (pintype "passive"))
    )
    (net (code "44") (name "Net-(D15-PadA)") (class "Default")
      (node (ref "D15") (pin "A") (pinfunction "A_A") (pintype "passive"))
      (node (ref "R22") (pin "1") (pinfunction "1_1") (pintype "passive"))
    )
    (net (code "45") (name "Net-(D16-PadA)") (class "Default")
      (node (ref "D16") (pin "A") (pinfunction "A_A") (pintype "passive"))
      (node (ref "R23") (pin "1") (pinfunction "1_1") (pintype "passive"))
    )
    (net (code "46") (name "Net-(D17-PadA)") (class "Default")
      (node (ref "D17") (pin "A") (pinfunction "A_A") (pintype "passive"))
      (node (ref "R36") (pin "1") (pinfunction "1_1") (pintype "passive"))
    )
    (net (code "47") (name "Net-(D18-PadA)") (class "Default")
      (node (ref "D18") (pin "A") (pinfunction "A_A") (pintype "passive"))
      (node (ref "R37") (pin "1") (pinfunction "1_1") (pintype "passive"))
    )
    (net (code "48") (name "Net-(JTAG-EMU0)") (class "Default")
      (node (ref "JTAG") (pin "13") (pinfunction "EMU0_13") (pintype "bidirectional"))
      (node (ref "R2") (pin "2") (pinfunction "2_2") (pintype "passive"))
    )
    (net (code "49") (name "Net-(JTAG-EMU1)") (class "Default")
      (node (ref "JTAG") (pin "14") (pinfunction "EMU1_14") (pintype "bidirectional"))
      (node (ref "R3") (pin "2") (pinfunction "2_2") (pintype "passive"))
    )
    (net (code "50") (name "Net-(SW1-IN1)") (class "Default")
      (node (ref "R32") (pin "2") (pinfunction "2_2") (pintype "passive"))
      (node (ref "SW1") (pin "1") (pinfunction "IN1_1") (pintype "bidirectional"))
    )
    (net (code "51") (name "Net-(SW1-IN3)") (class "Default")
      (node (ref "R33") (pin "2") (pinfunction "2_2") (pintype "passive"))
      (node (ref "SW1") (pin "3") (pinfunction "IN3_3") (pintype "bidirectional"))
    )
    (net (code "52") (name "Net-(SW2-IN1)") (class "Default")
      (node (ref "R34") (pin "2") (pinfunction "2_2") (pintype "passive"))
      (node (ref "SW2") (pin "1") (pinfunction "IN1_1") (pintype "bidirectional"))
    )
    (net (code "53") (name "Net-(SW2-IN3)") (class "Default")
      (node (ref "R35") (pin "2") (pinfunction "2_2") (pintype "passive"))
      (node (ref "SW2") (pin "3") (pinfunction "IN3_3") (pintype "bidirectional"))
    )
    (net (code "54") (name "Net-(U3-1Y1)") (class "Default")
      (node (ref "U$4") (pin "2") (pinfunction "2_2") (pintype "bidirectional"))
      (node (ref "U3") (pin "1") (pinfunction "1Y1_1") (pintype "tri_state"))
    )
    (net (code "55") (name "Net-(U3-1Y2)") (class "Default")
      (node (ref "U$4") (pin "3") (pinfunction "3_3") (pintype "bidirectional"))
      (node (ref "U3") (pin "3") (pinfunction "1Y2_3") (pintype "tri_state"))
    )
    (net (code "56") (name "Net-(U3-1Y3)") (class "Default")
      (node (ref "U$4") (pin "4") (pinfunction "4_4") (pintype "bidirectional"))
      (node (ref "U3") (pin "4") (pinfunction "1Y3_4") (pintype "tri_state"))
    )
    (net (code "57") (name "Net-(U3-1Y4)") (class "Default")
      (node (ref "U$4") (pin "5") (pinfunction "5_5") (pintype "bidirectional"))
      (node (ref "U3") (pin "6") (pinfunction "1Y4_6") (pintype "tri_state"))
    )
    (net (code "58") (name "Net-(U3-2Y1)") (class "Default")
      (node (ref "U$4") (pin "6") (pinfunction "6_6") (pintype "bidirectional"))
      (node (ref "U3") (pin "7") (pinfunction "2Y1_7") (pintype "tri_state"))
    )
    (net (code "59") (name "Net-(U3-2Y2)") (class "Default")
      (node (ref "U$4") (pin "7") (pinfunction "7_7") (pintype "bidirectional"))
      (node (ref "U3") (pin "9") (pinfunction "2Y2_9") (pintype "tri_state"))
    )
    (net (code "60") (name "Net-(U3-2Y3)") (class "Default")
      (node (ref "U$4") (pin "8") (pinfunction "8_8") (pintype "bidirectional"))
      (node (ref "U3") (pin "10") (pinfunction "2Y3_10") (pintype "tri_state"))
    )
    (net (code "61") (name "Net-(U3-2Y4)") (class "Default")
      (node (ref "U$4") (pin "9") (pinfunction "9_9") (pintype "bidirectional"))
      (node (ref "U3") (pin "12") (pinfunction "2Y4_12") (pintype "tri_state"))
    )
    (net (code "62") (name "Net-(U5-1A1)") (class "Default")
      (node (ref "U$8") (pin "9") (pinfunction "9_9") (pintype "bidirectional"))
      (node (ref "U5") (pin "23") (pinfunction "1A1_23") (pintype "input"))
    )
    (net (code "63") (name "Net-(U5-1A2)") (class "Default")
      (node (ref "U$8") (pin "8") (pinfunction "8_8") (pintype "bidirectional"))
      (node (ref "U5") (pin "22") (pinfunction "1A2_22") (pintype "input"))
    )
    (net (code "64") (name "Net-(U5-1A3)") (class "Default")
      (node (ref "U$8") (pin "7") (pinfunction "7_7") (pintype "bidirectional"))
      (node (ref "U5") (pin "20") (pinfunction "1A3_20") (pintype "input"))
    )
    (net (code "65") (name "Net-(U5-1A4)") (class "Default")
      (node (ref "U$8") (pin "6") (pinfunction "6_6") (pintype "bidirectional"))
      (node (ref "U5") (pin "19") (pinfunction "1A4_19") (pintype "input"))
    )
    (net (code "66") (name "Net-(U5-2A1)") (class "Default")
      (node (ref "U$8") (pin "5") (pinfunction "5_5") (pintype "bidirectional"))
      (node (ref "U5") (pin "18") (pinfunction "2A1_18") (pintype "input"))
    )
    (net (code "67") (name "Net-(U5-2A2)") (class "Default")
      (node (ref "U$8") (pin "4") (pinfunction "4_4") (pintype "bidirectional"))
      (node (ref "U5") (pin "17") (pinfunction "2A2_17") (pintype "input"))
    )
    (net (code "68") (name "Net-(U5-2A3)") (class "Default")
      (node (ref "U$8") (pin "3") (pinfunction "3_3") (pintype "bidirectional"))
      (node (ref "U5") (pin "15") (pinfunction "2A3_15") (pintype "input"))
    )
    (net (code "69") (name "Net-(U5-2A4)") (class "Default")
      (node (ref "U$8") (pin "2") (pinfunction "2_2") (pintype "bidirectional"))
      (node (ref "U5") (pin "14") (pinfunction "2A4_14") (pintype "input"))
    )
    (net (code "70") (name "Net-(U9-B)") (class "Default")
      (node (ref "R37") (pin "2") (pinfunction "2_2") (pintype "passive"))
      (node (ref "U9") (pin "4") (pinfunction "B_4") (pintype "bidirectional"))
      (node (ref "USB") (pin "VBUS") (pinfunction "VBUS_VBUS") (pintype "bidirectional"))
    )
    (net (code "71") (name "RESET") (class "Default")
      (node (ref "C12") (pin "1") (pinfunction "1_1") (pintype "passive"))
      (node (ref "R6") (pin "1") (pinfunction "1_1") (pintype "passive"))
      (node (ref "U$7") (pin "P$2") (pinfunction "2_P$2") (pintype "bidirectional"))
      (node (ref "U1") (pin "9") (pinfunction "*XRS_9") (pintype "bidirectional"))
    )
    (net (code "72") (name "RUNSEL") (class "Default")
      (node (ref "SW2") (pin "2") (pinfunction "OUT2_2") (pintype "bidirectional"))
      (node (ref "U1") (pin "7") (pinfunction "GPIO4/EPWM3A_7") (pintype "bidirectional"))
    )
    (net (code "73") (name "SPICLK") (class "Default")
      (node (ref "JP2") (pin "1") (pinfunction "1_1") (pintype "bidirectional"))
      (node (ref "U1") (pin "76") (pinfunction "GPIO14/*TZ3/SCITXDB/SPICLKB_76") (pintype "bidirectional"))
      (node (ref "U8") (pin "P6") (pinfunction "SCK_P6") (pintype "bidirectional"))
    )
    (net (code "74") (name "SPISIMO") (class "Default")
      (node (ref "JP2") (pin "2") (pinfunction "2_2") (pintype "bidirectional"))
      (node (ref "U1") (pin "77") (pinfunction "GPIO24/ECAP1/SPISIMOB_77") (pintype "bidirectional"))
      (node (ref "U8") (pin "P5") (pinfunction "SI_P5") (pintype "bidirectional"))
    )
    (net (code "75") (name "SPISOMI") (class "Default")
      (node (ref "JP2") (pin "3") (pinfunction "3_3") (pintype "bidirectional"))
      (node (ref "U1") (pin "75") (pinfunction "GPIO13/*TZ2/SPISOMIB_75") (pintype "bidirectional"))
      (node (ref "U8") (pin "P2") (pinfunction "SO_P2") (pintype "bidirectional"))
    )
    (net (code "76") (name "SW1") (class "Default")
      (node (ref "R24") (pin "2") (pinfunction "2_2") (pintype "passive"))
      (node (ref "U$9") (pin "1") (pinfunction "IN1_1") (pintype "bidirectional"))
      (node (ref "U6") (pin "2") (pinfunction "A1_2") (pintype "input"))
    )
    (net (code "77") (name "SW2") (class "Default")
      (node (ref "R25") (pin "2") (pinfunction "2_2") (pintype "passive"))
      (node (ref "U$9") (pin "2") (pinfunction "IN2_2") (pintype "bidirectional"))
      (node (ref "U6") (pin "3") (pinfunction "A2_3") (pintype "input"))
    )
    (net (code "78") (name "SW3") (class "Default")
      (node (ref "R26") (pin "2") (pinfunction "2_2") (pintype "passive"))
      (node (ref "U$9") (pin "3") (pinfunction "IN3_3") (pintype "bidirectional"))
      (node (ref "U6") (pin "4") (pinfunction "A3_4") (pintype "input"))
    )
    (net (code "79") (name "SW4") (class "Default")
      (node (ref "R27") (pin "2") (pinfunction "2_2") (pintype "passive"))
      (node (ref "U$9") (pin "4") (pinfunction "IN4_4") (pintype "bidirectional"))
      (node (ref "U6") (pin "5") (pinfunction "A4_5") (pintype "input"))
    )
    (net (code "80") (name "SW5") (class "Default")
      (node (ref "R28") (pin "2") (pinfunction "2_2") (pintype "passive"))
      (node (ref "U$9") (pin "5") (pinfunction "IN5_5") (pintype "bidirectional"))
      (node (ref "U6") (pin "6") (pinfunction "A5_6") (pintype "input"))
    )
    (net (code "81") (name "SW6") (class "Default")
      (node (ref "R29") (pin "2") (pinfunction "2_2") (pintype "passive"))
      (node (ref "U$9") (pin "6") (pinfunction "IN6_6") (pintype "bidirectional"))
      (node (ref "U6") (pin "7") (pinfunction "A6_7") (pintype "input"))
    )
    (net (code "82") (name "SW7") (class "Default")
      (node (ref "R30") (pin "2") (pinfunction "2_2") (pintype "passive"))
      (node (ref "U$9") (pin "7") (pinfunction "IN7_7") (pintype "bidirectional"))
      (node (ref "U6") (pin "8") (pinfunction "A7_8") (pintype "input"))
    )
    (net (code "83") (name "SW8") (class "Default")
      (node (ref "R31") (pin "2") (pinfunction "2_2") (pintype "passive"))
      (node (ref "U$9") (pin "8") (pinfunction "IN8_8") (pintype "bidirectional"))
      (node (ref "U6") (pin "9") (pinfunction "A8_9") (pintype "input"))
    )
    (net (code "84") (name "TCK") (class "Default")
      (node (ref "JTAG") (pin "11") (pinfunction "TCK_11") (pintype "bidirectional"))
      (node (ref "JTAG") (pin "9") (pinfunction "TCK_RET_9") (pintype "bidirectional"))
      (node (ref "U1") (pin "54") (pinfunction "GPIO38/XCLKIN/TCK_54") (pintype "bidirectional"))
    )
    (net (code "85") (name "TDI") (class "Default")
      (node (ref "JTAG") (pin "3") (pinfunction "TDI_3") (pintype "bidirectional"))
      (node (ref "U1") (pin "57") (pinfunction "GPIO35/TDI_57") (pintype "bidirectional"))
    )
    (net (code "86") (name "TDO") (class "Default")
      (node (ref "JTAG") (pin "7") (pinfunction "TDO_7") (pintype "bidirectional"))
      (node (ref "U1") (pin "56") (pinfunction "GPIO37/TDO_56") (pintype "bidirectional"))
    )
    (net (code "87") (name "TMS") (class "Default")
      (node (ref "JTAG") (pin "1") (pinfunction "TMS_1") (pintype "bidirectional"))
      (node (ref "U1") (pin "58") (pinfunction "GPIO36/TMS_58") (pintype "bidirectional"))
    )
    (net (code "88") (name "UCIN1") (class "Default")
      (node (ref "U1") (pin "31") (pinfunction "GPIO25/ECAP2/SPISOMIB_31") (pintype "bidirectional"))
      (node (ref "U4") (pin "21") (pinfunction "B1_21") (pintype "bidirectional"))
    )
    (net (code "89") (name "UCIN2") (class "Default")
      (node (ref "U1") (pin "32") (pinfunction "GPIO31/CANTXA/EPWM8A_32") (pintype "bidirectional"))
      (node (ref "U4") (pin "20") (pinfunction "B3_20") (pintype "bidirectional"))
    )
    (net (code "90") (name "UCIN3") (class "Default")
      (node (ref "U1") (pin "33") (pinfunction "GPIO30/CANRXA/EPWM7A_33") (pintype "bidirectional"))
      (node (ref "U4") (pin "19") (pinfunction "B3_2_19") (pintype "bidirectional"))
    )
    (net (code "91") (name "UCIN4") (class "Default")
      (node (ref "U1") (pin "34") (pinfunction "GPIO29/SCITXDA/SCLA/*TZ3_34") (pintype "bidirectional"))
      (node (ref "U4") (pin "18") (pinfunction "B4_18") (pintype "bidirectional"))
    )
    (net (code "92") (name "UCIN5") (class "Default")
      (node (ref "U1") (pin "35") (pinfunction "GPIO12/*TZ1/SCITXDA/SPISIMOB_35") (pintype "bidirectional"))
      (node (ref "U4") (pin "17") (pinfunction "B5_17") (pintype "bidirectional"))
    )
    (net (code "93") (name "UCIN6") (class "Default")
      (node (ref "U1") (pin "39") (pinfunction "GPIO9/EPWM5B/SCITXDB/ECAP3_39") (pintype "bidirectional"))
      (node (ref "U4") (pin "16") (pinfunction "B6_16") (pintype "bidirectional"))
    )
    (net (code "94") (name "UCIN7") (class "Default")
      (node (ref "U1") (pin "40") (pinfunction "GPIO28/SCIRXDA/SDAA/*TZ2_40") (pintype "bidirectional"))
      (node (ref "U4") (pin "15") (pinfunction "B7_15") (pintype "bidirectional"))
    )
    (net (code "95") (name "UCIN8") (class "Default")
      (node (ref "U1") (pin "41") (pinfunction "GPIO18/SPICLKA/SCITXDB/XCLKOUT_41") (pintype "bidirectional"))
      (node (ref "U4") (pin "14") (pinfunction "B8_14") (pintype "bidirectional"))
    )
    (net (code "96") (name "UCOUT1") (class "Default")
      (node (ref "U1") (pin "42") (pinfunction "GPIO17/SPISOMIA/*TZ3_42") (pintype "bidirectional"))
      (node (ref "U2") (pin "21") (pinfunction "B1_21") (pintype "bidirectional"))
    )
    (net (code "97") (name "UCOUT2") (class "Default")
      (node (ref "U1") (pin "43") (pinfunction "GPIO8/EPWM5A/*ADCSOCAO_43") (pintype "bidirectional"))
      (node (ref "U2") (pin "20") (pinfunction "B3_20") (pintype "bidirectional"))
    )
    (net (code "98") (name "UCOUT3") (class "Default")
      (node (ref "U1") (pin "44") (pinfunction "GPIO16/SPISIMOA/*TZ2_44") (pintype "bidirectional"))
      (node (ref "U2") (pin "19") (pinfunction "B3_2_19") (pintype "bidirectional"))
    )
    (net (code "99") (name "UCOUT4") (class "Default")
      (node (ref "U1") (pin "45") (pinfunction "GPIO7/EPWM4B/SCIRXDA/ECAP2_45") (pintype "bidirectional"))
      (node (ref "U2") (pin "18") (pinfunction "B4_18") (pintype "bidirectional"))
    )
    (net (code "100") (name "UCOUT5") (class "Default")
      (node (ref "U1") (pin "46") (pinfunction "GPIO6/EPWM4A/EPWMSYNCI/EPWMSYNCO_46") (pintype "bidirectional"))
      (node (ref "U2") (pin "17") (pinfunction "B5_17") (pintype "bidirectional"))
    )
    (net (code "101") (name "UCOUT6") (class "Default")
      (node (ref "U1") (pin "52") (pinfunction "GPIO19/XCLKIN/*SPISTEA/SCIRXDB/ECAP1_52") (pintype "bidirectional"))
      (node (ref "U2") (pin "16") (pinfunction "B6_16") (pintype "bidirectional"))
    )
    (net (code "102") (name "UCOUT7") (class "Default")
      (node (ref "U1") (pin "53") (pinfunction "GPIO39_53") (pintype "bidirectional"))
      (node (ref "U2") (pin "15") (pinfunction "B7_15") (pintype "bidirectional"))
    )
    (net (code "103") (name "UCOUT8") (class "Default")
      (node (ref "U1") (pin "59") (pinfunction "GPIO11/EPWM6B/SCIRXDB/ECAP1_59") (pintype "bidirectional"))
      (node (ref "U2") (pin "14") (pinfunction "B8_14") (pintype "bidirectional"))
    )
    (net (code "104") (name "USBMON") (class "Default")
      (node (ref "U1") (pin "1") (pinfunction "GPIO23/EQEP1I/MFSXA/SCIRXDB_1") (pintype "bidirectional"))
      (node (ref "U9") (pin "3") (pinfunction "A_3") (pintype "bidirectional"))
    )
    (net (code "105") (name "USB_N") (class "Default")
      (node (ref "U1") (pin "61") (pinfunction "GPIO27/HRCAP2/*SPISTEB/USB0DM_61") (pintype "bidirectional"))
      (node (ref "USB") (pin "D-") (pinfunction "D-_D-") (pintype "bidirectional"))
    )
    (net (code "106") (name "USB_P") (class "Default")
      (node (ref "R4") (pin "1") (pinfunction "1_1") (pintype "passive"))
      (node (ref "U1") (pin "62") (pinfunction "GPIO26/ECAP3/SPICLKB/USB0DP_62") (pintype "bidirectional"))
      (node (ref "USB") (pin "D+") (pinfunction "D+_D+") (pintype "bidirectional"))
    )
    (net (code "107") (name "VDD") (class "Default")
      (node (ref "C10") (pin "1") (pinfunction "1_1") (pintype "passive"))
      (node (ref "C11") (pin "1") (pinfunction "1_1") (pintype "passive"))
      (node (ref "C3") (pin "1") (pinfunction "1_1") (pintype "passive"))
      (node (ref "C6") (pin "1") (pinfunction "1_1") (pintype "passive"))
      (node (ref "C8") (pin "1") (pinfunction "1_1") (pintype "passive"))
      (node (ref "C9") (pin "1") (pinfunction "1_1") (pintype "passive"))
      (node (ref "U1") (pin "12") (pinfunction "VDD_3_12") (pintype "power_in"))
      (node (ref "U1") (pin "2") (pinfunction "VDD_2_2") (pintype "power_in"))
      (node (ref "U1") (pin "29") (pinfunction "VDD_4_29") (pintype "power_in"))
      (node (ref "U1") (pin "51") (pinfunction "VDD_5_51") (pintype "power_in"))
      (node (ref "U1") (pin "65") (pinfunction "VDD_6_65") (pintype "power_in"))
      (node (ref "U1") (pin "72") (pinfunction "VDD_72") (pintype "power_in"))
    )
    (net (code "108") (name "X1") (class "Default")
      (node (ref "C1") (pin "1") (pinfunction "1_1") (pintype "passive"))
      (node (ref "CRYSTAL") (pin "1") (pinfunction "CLK1_1") (pintype "bidirectional"))
      (node (ref "U1") (pin "48") (pinfunction "X1_48") (pintype "input"))
    )
    (net (code "109") (name "X2") (class "Default")
      (node (ref "C2") (pin "1") (pinfunction "1_1") (pintype "passive"))
      (node (ref "CRYSTAL") (pin "3") (pinfunction "CLK2_3") (pintype "bidirectional"))
      (node (ref "U1") (pin "47") (pinfunction "X2_47") (pintype "output"))
    )
    (net (code "110") (name "unconnected-(C7-Pad1)") (class "Default")
      (node (ref "C7") (pin "1") (pinfunction "1_1") (pintype "passive"))
    )
    (net (code "111") (name "unconnected-(U1-ADCINA0-Pad19)") (class "Default")
      (node (ref "U1") (pin "19") (pinfunction "ADCINA0_19") (pintype "passive"))
    )
    (net (code "112") (name "unconnected-(U1-ADCINA1-Pad18)") (class "Default")
      (node (ref "U1") (pin "18") (pinfunction "ADCINA1_18") (pintype "input"))
    )
    (net (code "113") (name "unconnected-(U1-ADCINA2{slash}COMP1A{slash}AIO2-Pad17)") (class "Default")
      (node (ref "U1") (pin "17") (pinfunction "ADCINA2/COMP1A/AIO2_17") (pintype "bidirectional"))
    )
    (net (code "114") (name "unconnected-(U1-ADCINA4{slash}COMP2A{slash}AIO4-Pad16)") (class "Default")
      (node (ref "U1") (pin "16") (pinfunction "ADCINA4/COMP2A/AIO4_16") (pintype "bidirectional"))
    )
    (net (code "115") (name "unconnected-(U1-ADCINA5-Pad15)") (class "Default")
      (node (ref "U1") (pin "15") (pinfunction "ADCINA5_15") (pintype "input"))
    )
    (net (code "116") (name "unconnected-(U1-ADCINA6{slash}COMP3A{slash}AIO6-Pad14)") (class "Default")
      (node (ref "U1") (pin "14") (pinfunction "ADCINA6/COMP3A/AIO6_14") (pintype "bidirectional"))
    )
    (net (code "117") (name "unconnected-(U1-ADCINB0-Pad22)") (class "Default")
      (node (ref "U1") (pin "22") (pinfunction "ADCINB0_22") (pintype "input"))
    )
    (net (code "118") (name "unconnected-(U1-ADCINB1-Pad23)") (class "Default")
      (node (ref "U1") (pin "23") (pinfunction "ADCINB1_23") (pintype "input"))
    )
    (net (code "119") (name "unconnected-(U1-ADCINB2{slash}COMP1B{slash}AIO10-Pad24)") (class "Default")
      (node (ref "U1") (pin "24") (pinfunction "ADCINB2/COMP1B/AIO10_24") (pintype "bidirectional"))
    )
    (net (code "120") (name "unconnected-(U1-ADCINB4{slash}COMP2B{slash}AIO12-Pad25)") (class "Default")
      (node (ref "U1") (pin "25") (pinfunction "ADCINB4/COMP2B/AIO12_25") (pintype "bidirectional"))
    )
    (net (code "121") (name "unconnected-(U1-ADCINB5-Pad26)") (class "Default")
      (node (ref "U1") (pin "26") (pinfunction "ADCINB5_26") (pintype "input"))
    )
    (net (code "122") (name "unconnected-(U1-ADCINB6{slash}COMP3B{slash}AIO14-Pad27)") (class "Default")
      (node (ref "U1") (pin "27") (pinfunction "ADCINB6/COMP3B/AIO14_27") (pintype "bidirectional"))
    )
    (net (code "123") (name "unconnected-(U1-GPIO0{slash}EPWM1A-Pad69)") (class "Default")
      (node (ref "U1") (pin "69") (pinfunction "GPIO0/EPWM1A_69") (pintype "bidirectional"))
    )
    (net (code "124") (name "unconnected-(U1-GPIO1{slash}EPWM1B{slash}COMP1OUT-Pad68)") (class "Default")
      (node (ref "U1") (pin "68") (pinfunction "GPIO1/EPWM1B/COMP1OUT_68") (pintype "bidirectional"))
    )
    (net (code "125") (name "unconnected-(U1-GPIO2{slash}EPWM2A-Pad67)") (class "Default")
      (node (ref "U1") (pin "67") (pinfunction "GPIO2/EPWM2A_67") (pintype "bidirectional"))
    )
    (net (code "126") (name "unconnected-(U1-GPIO3{slash}EPWM2B{slash}SPISOMIA{slash}COMP2OUT-Pad66)") (class "Default")
      (node (ref "U1") (pin "66") (pinfunction "GPIO3/EPWM2B/SPISOMIA/COMP2OUT_66") (pintype "bidirectional"))
    )
    (net (code "127") (name "unconnected-(U1-GPIO5{slash}EPWM3B{slash}SPISIMOA{slash}ECAP1-Pad8)") (class "Default")
      (node (ref "U1") (pin "8") (pinfunction "GPIO5/EPWM3B/SPISIMOA/ECAP1_8") (pintype "bidirectional"))
    )
    (net (code "128") (name "unconnected-(U1-GPIO15{slash}ECAP2{slash}SCIRXDB{slash}*SPISTEB-Pad70)") (class "Default")
      (node (ref "U1") (pin "70") (pinfunction "GPIO15/ECAP2/SCIRXDB/*SPISTEB_70") (pintype "bidirectional"))
    )
    (net (code "129") (name "unconnected-(U1-GPIO34{slash}COMP2OUT{slash}COMP3OUT-Pad55)") (class "Default")
      (node (ref "U1") (pin "55") (pinfunction "GPIO34/COMP2OUT/COMP3OUT_55") (pintype "bidirectional"))
    )
    (net (code "130") (name "unconnected-(U1-TEST2-Pad36)") (class "Default")
      (node (ref "U1") (pin "36") (pinfunction "TEST2_36") (pintype "bidirectional"))
    )
    (net (code "131") (name "unconnected-(U7-NC-Pad1)") (class "Default")
      (node (ref "U7") (pin "1") (pinfunction "NC_1") (pintype "passive"))
    )
  )
)
